# keyboard.net
KiCad netlist of a schematic drawn in EAGLE
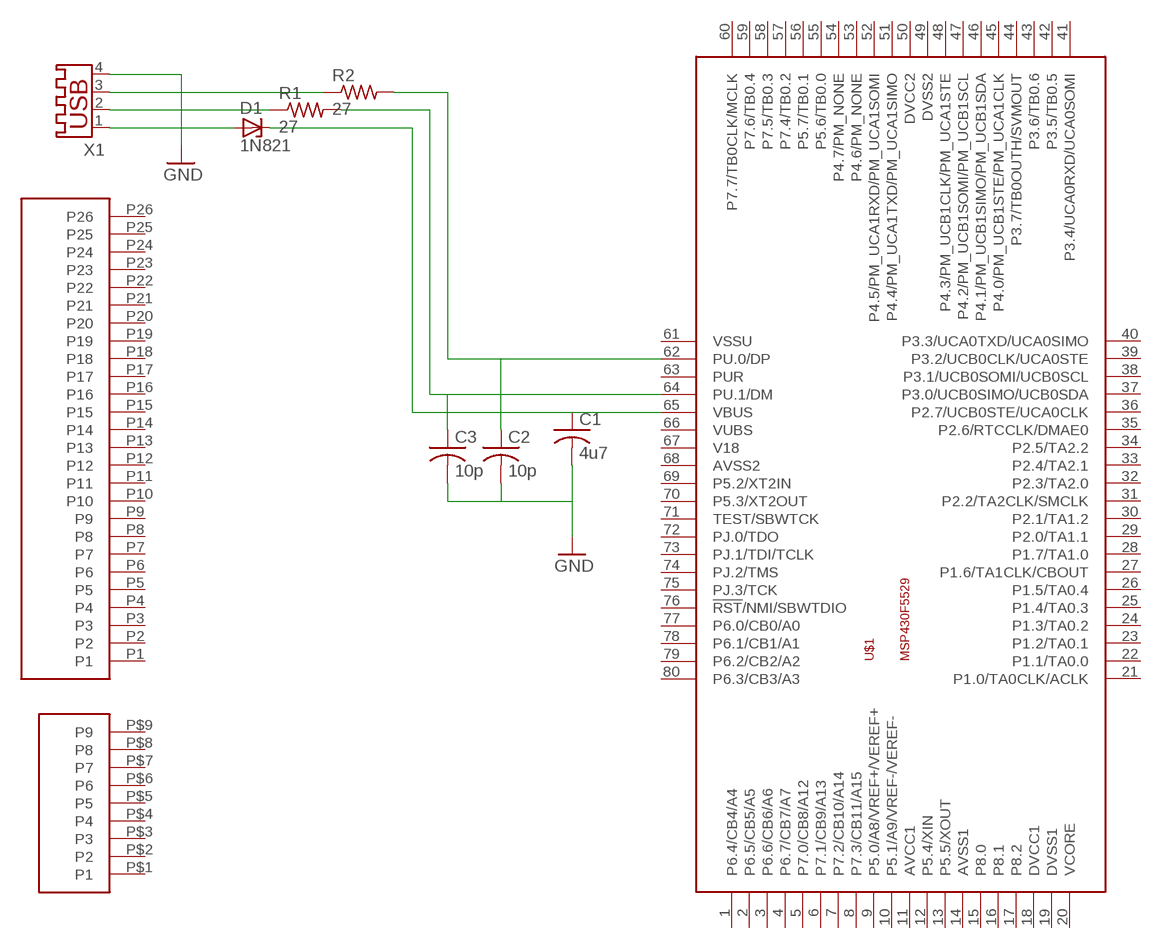
[diagram p0: schematic, sheet 1]

(export (version "E")
  (design (tool "Eeschema 10.0.6"))
  (components
    (comp (ref "C1")
      (value "4u7")
      (footprint "eagle-import:C0805")
      (libsource (lib "eagle-import") (part "C-USC0805"))
    )
    (comp (ref "C2")
      (value "10p")
      (footprint "eagle-import:C0805")
      (libsource (lib "eagle-import") (part "C-USC0805"))
    )
    (comp (ref "C3")
      (value "10p")
      (footprint "eagle-import:C0805")
      (libsource (lib "eagle-import") (part "C-USC0805"))
    )
    (comp (ref "D1")
      (value "1N821")
      (footprint "eagle-import:DO35Z10")
      (libsource (lib "eagle-import") (part "1N821"))
    )
    (comp (ref "R1")
      (value "27")
      (footprint "eagle-import:R0603")
      (libsource (lib "eagle-import") (part "R-US_R0603"))
    )
    (comp (ref "R2")
      (value "27")
      (footprint "eagle-import:R0603")
      (libsource (lib "eagle-import") (part "R-US_R0603"))
    )
    (comp (ref "U$1")
      (value "MSP430F5529")
      (footprint "eagle-import:PN_S-PQFP-G80")
      (libsource (lib "eagle-import") (part "MSP430F5529"))
    )
    (comp (ref "U$2")
      (value "52808-267126")
      (footprint "eagle-import:SD-52808-025")
      (libsource (lib "eagle-import") (part "52808-267126"))
    )
    (comp (ref "U$3")
      (value "52806-0910")
      (footprint "eagle-import:SD-52806-09")
      (libsource (lib "eagle-import") (part "52806-0910"))
    )
    (comp (ref "X1")
      (value "USB-A003")
      (footprint "eagle-import:USB-A003")
      (libsource (lib "eagle-import") (part "USB-A003"))
    )
  )
  (nets
    (net (code "1") (name "GND") (class "Default")
      (node (ref "C1") (pin "2") (pinfunction "2_2") (pintype "passive"))
      (node (ref "C2") (pin "2") (pinfunction "2_2") (pintype "passive"))
      (node (ref "C3") (pin "2") (pinfunction "2_2") (pintype "passive"))
      (node (ref "X1") (pin "4") (pinfunction "4_4") (pintype "passive"))
    )
    (net (code "2") (name "Net-(D1-PadA)") (class "Default")
      (node (ref "D1") (pin "A") (pinfunction "A_A") (pintype "passive"))
      (node (ref "X1") (pin "1") (pinfunction "1_1") (pintype "passive"))
    )
    (net (code "3") (name "Net-(R1-Pad1)") (class "Default")
      (node (ref "R1") (pin "1") (pinfunction "1_1") (pintype "passive"))
      (node (ref "X1") (pin "2") (pinfunction "2_2") (pintype "passive"))
    )
    (net (code "4") (name "Net-(R2-Pad1)") (class "Default")
      (node (ref "R2") (pin "1") (pinfunction "1_1") (pintype "passive"))
      (node (ref "X1") (pin "3") (pinfunction "3_3") (pintype "passive"))
    )
    (net (code "5") (name "Net-(U$1-PU.0{slash}DP)") (class "Default")
      (node (ref "C2") (pin "1") (pinfunction "1_1") (pintype "passive"))
      (node (ref "R2") (pin "2") (pinfunction "2_2") (pintype "passive"))
      (node (ref "U$1") (pin "62") (pinfunction "PU.0/DP_62") (pintype "bidirectional"))
    )
    (net (code "6") (name "Net-(U$1-PU.1{slash}DM)") (class "Default")
      (node (ref "C3") (pin "1") (pinfunction "1_1") (pintype "passive"))
      (node (ref "R1") (pin "2") (pinfunction "2_2") (pintype "passive"))
      (node (ref "U$1") (pin "64") (pinfunction "PU.1/DM_64") (pintype "bidirectional"))
    )
    (net (code "7") (name "Net-(U$1-VBUS)") (class "Default")
      (node (ref "C1") (pin "1") (pinfunction "1_1") (pintype "passive"))
      (node (ref "D1") (pin "C") (pinfunction "C_C") (pintype "passive"))
      (node (ref "U$1") (pin "65") (pinfunction "VBUS_65") (pintype "bidirectional"))
    )
    (net (code "8") (name "unconnected-(U$1-AVCC1-Pad11)") (class "Default")
      (node (ref "U$1") (pin "11") (pinfunction "AVCC1_11") (pintype "bidirectional"))
    )
    (net (code "9") (name "unconnected-(U$1-AVSS1-Pad14)") (class "Default")
      (node (ref "U$1") (pin "14") (pinfunction "AVSS1_14") (pintype "bidirectional"))
    )
    (net (code "10") (name "unconnected-(U$1-AVSS2-Pad68)") (class "Default")
      (node (ref "U$1") (pin "68") (pinfunction "AVSS2_68") (pintype "bidirectional"))
    )
    (net (code "11") (name "unconnected-(U$1-DVCC1-Pad18)") (class "Default")
      (node (ref "U$1") (pin "18") (pinfunction "DVCC1_18") (pintype "bidirectional"))
    )
    (net (code "12") (name "unconnected-(U$1-DVCC2-Pad50)") (class "Default")
      (node (ref "U$1") (pin "50") (pinfunction "DVCC2_50") (pintype "bidirectional"))
    )
    (net (code "13") (name "unconnected-(U$1-DVSS1-Pad19)") (class "Default")
      (node (ref "U$1") (pin "19") (pinfunction "DVSS1_19") (pintype "bidirectional"))
    )
    (net (code "14") (name "unconnected-(U$1-DVSS2-Pad49)") (class "Default")
      (node (ref "U$1") (pin "49") (pinfunction "DVSS2_49") (pintype "bidirectional"))
    )
    (net (code "15") (name "unconnected-(U$1-P1.0{slash}TA0CLK{slash}ACLK-Pad21)") (class "Default")
      (node (ref "U$1") (pin "21") (pinfunction "P1.0/TA0CLK/ACLK_21") (pintype "bidirectional"))
    )
    (net (code "16") (name "unconnected-(U$1-P1.1{slash}TA0.0-Pad22)") (class "Default")
      (node (ref "U$1") (pin "22") (pinfunction "P1.1/TA0.0_22") (pintype "bidirectional"))
    )
    (net (code "17") (name "unconnected-(U$1-P1.2{slash}TA0.1-Pad23)") (class "Default")
      (node (ref "U$1") (pin "23") (pinfunction "P1.2/TA0.1_23") (pintype "bidirectional"))
    )
    (net (code "18") (name "unconnected-(U$1-P1.3{slash}TA0.2-Pad24)") (class "Default")
      (node (ref "U$1") (pin "24") (pinfunction "P1.3/TA0.2_24") (pintype "bidirectional"))
    )
    (net (code "19") (name "unconnected-(U$1-P1.4{slash}TA0.3-Pad25)") (class "Default")
      (node (ref "U$1") (pin "25") (pinfunction "P1.4/TA0.3_25") (pintype "bidirectional"))
    )
    (net (code "20") (name "unconnected-(U$1-P1.5{slash}TA0.4-Pad26)") (class "Default")
      (node (ref "U$1") (pin "26") (pinfunction "P1.5/TA0.4_26") (pintype "bidirectional"))
    )
    (net (code "21") (name "unconnected-(U$1-P1.6{slash}TA1CLK{slash}CBOUT-Pad27)") (class "Default")
      (node (ref "U$1") (pin "27") (pinfunction "P1.6/TA1CLK/CBOUT_27") (pintype "bidirectional"))
    )
    (net (code "22") (name "unconnected-(U$1-P1.7{slash}TA1.0-Pad28)") (class "Default")
      (node (ref "U$1") (pin "28") (pinfunction "P1.7/TA1.0_28") (pintype "bidirectional"))
    )
    (net (code "23") (name "unconnected-(U$1-P2.0{slash}TA1.1-Pad29)") (class "Default")
      (node (ref "U$1") (pin "29") (pinfunction "P2.0/TA1.1_29") (pintype "bidirectional"))
    )
    (net (code "24") (name "unconnected-(U$1-P2.1{slash}TA1.2-Pad30)") (class "Default")
      (node (ref "U$1") (pin "30") (pinfunction "P2.1/TA1.2_30") (pintype "bidirectional"))
    )
    (net (code "25") (name "unconnected-(U$1-P2.2{slash}TA2CLK{slash}SMCLK-Pad31)") (class "Default")
      (node (ref "U$1") (pin "31") (pinfunction "P2.2/TA2CLK/SMCLK_31") (pintype "bidirectional"))
    )
    (net (code "26") (name "unconnected-(U$1-P2.3{slash}TA2.0-Pad32)") (class "Default")
      (node (ref "U$1") (pin "32") (pinfunction "P2.3/TA2.0_32") (pintype "bidirectional"))
    )
    (net (code "27") (name "unconnected-(U$1-P2.4{slash}TA2.1-Pad33)") (class "Default")
      (node (ref "U$1") (pin "33") (pinfunction "P2.4/TA2.1_33") (pintype "bidirectional"))
    )
    (net (code "28") (name "unconnected-(U$1-P2.5{slash}TA2.2-Pad34)") (class "Default")
      (node (ref "U$1") (pin "34") (pinfunction "P2.5/TA2.2_34") (pintype "bidirectional"))
    )
    (net (code "29") (name "unconnected-(U$1-P2.6{slash}RTCCLK{slash}DMAE0-Pad35)") (class "Default")
      (node (ref "U$1") (pin "35") (pinfunction "P2.6/RTCCLK/DMAE0_35") (pintype "bidirectional"))
    )
    (net (code "30") (name "unconnected-(U$1-P2.7{slash}UCB0STE{slash}UCA0CLK-Pad36)") (class "Default")
      (node (ref "U$1") (pin "36") (pinfunction "P2.7/UCB0STE/UCA0CLK_36") (pintype "bidirectional"))
    )
    (net (code "31") (name "unconnected-(U$1-P3.0{slash}UCB0SIMO{slash}UCB0SDA-Pad37)") (class "Default")
      (node (ref "U$1") (pin "37") (pinfunction "P3.0/UCB0SIMO/UCB0SDA_37") (pintype "bidirectional"))
    )
    (net (code "32") (name "unconnected-(U$1-P3.1{slash}UCB0SOMI{slash}UCB0SCL-Pad38)") (class "Default")
      (node (ref "U$1") (pin "38") (pinfunction "P3.1/UCB0SOMI/UCB0SCL_38") (pintype "bidirectional"))
    )
    (net (code "33") (name "unconnected-(U$1-P3.2{slash}UCB0CLK{slash}UCA0STE-Pad39)") (class "Default")
      (node (ref "U$1") (pin "39") (pinfunction "P3.2/UCB0CLK/UCA0STE_39") (pintype "bidirectional"))
    )
    (net (code "34") (name "unconnected-(U$1-P3.3{slash}UCA0TXD{slash}UCA0SIMO-Pad40)") (class "Default")
      (node (ref "U$1") (pin "40") (pinfunction "P3.3/UCA0TXD/UCA0SIMO_40") (pintype "bidirectional"))
    )
    (net (code "35") (name "unconnected-(U$1-P3.4{slash}UCA0RXD{slash}UCA0SOMI-Pad41)") (class "Default")
      (node (ref "U$1") (pin "41") (pinfunction "P3.4/UCA0RXD/UCA0SOMI_41") (pintype "bidirectional"))
    )
    (net (code "36") (name "unconnected-(U$1-P3.5{slash}TB0.5-Pad42)") (class "Default")
      (node (ref "U$1") (pin "42") (pinfunction "P3.5/TB0.5_42") (pintype "bidirectional"))
    )
    (net (code "37") (name "unconnected-(U$1-P3.6{slash}TB0.6-Pad43)") (class "Default")
      (node (ref "U$1") (pin "43") (pinfunction "P3.6/TB0.6_43") (pintype "bidirectional"))
    )
    (net (code "38") (name "unconnected-(U$1-P3.7{slash}TB0OUTH{slash}SVMOUT-Pad44)") (class "Default")
      (node (ref "U$1") (pin "44") (pinfunction "P3.7/TB0OUTH/SVMOUT_44") (pintype "bidirectional"))
    )
    (net (code "39") (name "unconnected-(U$1-P4.0{slash}PM_UCB1STE{slash}PM_UCA1CLK-Pad45)") (class "Default")
      (node (ref "U$1") (pin "45") (pinfunction "P4.0/PM_UCB1STE/PM_UCA1CLK_45") (pintype "bidirectional"))
    )
    (net (code "40") (name "unconnected-(U$1-P4.1{slash}PM_UCB1SIMO{slash}PM_UCB1SDA-Pad46)") (class "Default")
      (node (ref "U$1") (pin "46") (pinfunction "P4.1/PM_UCB1SIMO/PM_UCB1SDA_46") (pintype "bidirectional"))
    )
    (net (code "41") (name "unconnected-(U$1-P4.2{slash}PM_UCB1SOMI{slash}PM_UCB1SCL-Pad47)") (class "Default")
      (node (ref "U$1") (pin "47") (pinfunction "P4.2/PM_UCB1SOMI/PM_UCB1SCL_47") (pintype "bidirectional"))
    )
    (net (code "42") (name "unconnected-(U$1-P4.3{slash}PM_UCB1CLK{slash}PM_UCA1STE-Pad48)") (class "Default")
      (node (ref "U$1") (pin "48") (pinfunction "P4.3/PM_UCB1CLK/PM_UCA1STE_48") (pintype "bidirectional"))
    )
    (net (code "43") (name "unconnected-(U$1-P4.4{slash}PM_UCA1TXD{slash}PM_UCA1SIMO-Pad51)") (class "Default")
      (node (ref "U$1") (pin "51") (pinfunction "P4.4/PM_UCA1TXD/PM_UCA1SIMO_51") (pintype "bidirectional"))
    )
    (net (code "44") (name "unconnected-(U$1-P4.5{slash}PM_UCA1RXD{slash}PM_UCA1SOMI-Pad52)") (class "Default")
      (node (ref "U$1") (pin "52") (pinfunction "P4.5/PM_UCA1RXD/PM_UCA1SOMI_52") (pintype "bidirectional"))
    )
    (net (code "45") (name "unconnected-(U$1-P4.6{slash}PM_NONE-Pad53)") (class "Default")
      (node (ref "U$1") (pin "53") (pinfunction "P4.6/PM_NONE_53") (pintype "bidirectional"))
    )
    (net (code "46") (name "unconnected-(U$1-P4.7{slash}PM_NONE-Pad54)") (class "Default")
      (node (ref "U$1") (pin "54") (pinfunction "P4.7/PM_NONE_54") (pintype "bidirectional"))
    )
    (net (code "47") (name "unconnected-(U$1-P5.0{slash}A8{slash}VREF+{slash}VEREF+-Pad9)") (class "Default")
      (node (ref "U$1") (pin "9") (pinfunction "P5.0/A8/VREF+/VEREF+_9") (pintype "bidirectional"))
    )
    (net (code "48") (name "unconnected-(U$1-P5.1{slash}A9{slash}VREF-{slash}VEREF--Pad10)") (class "Default")
      (node (ref "U$1") (pin "10") (pinfunction "P5.1/A9/VREF-/VEREF-_10") (pintype "bidirectional"))
    )
    (net (code "49") (name "unconnected-(U$1-P5.2{slash}XT2IN-Pad69)") (class "Default")
      (node (ref "U$1") (pin "69") (pinfunction "P5.2/XT2IN_69") (pintype "bidirectional"))
    )
    (net (code "50") (name "unconnected-(U$1-P5.3{slash}XT2OUT-Pad70)") (class "Default")
      (node (ref "U$1") (pin "70") (pinfunction "P5.3/XT2OUT_70") (pintype "bidirectional"))
    )
    (net (code "51") (name "unconnected-(U$1-P5.4{slash}XIN-Pad12)") (class "Default")
      (node (ref "U$1") (pin "12") (pinfunction "P5.4/XIN_12") (pintype "bidirectional"))
    )
    (net (code "52") (name "unconnected-(U$1-P5.5{slash}XOUT-Pad13)") (class "Default")
      (node (ref "U$1") (pin "13") (pinfunction "P5.5/XOUT_13") (pintype "bidirectional"))
    )
    (net (code "53") (name "unconnected-(U$1-P5.6{slash}TB0.0-Pad55)") (class "Default")
      (node (ref "U$1") (pin "55") (pinfunction "P5.6/TB0.0_55") (pintype "bidirectional"))
    )
    (net (code "54") (name "unconnected-(U$1-P5.7{slash}TB0.1-Pad56)") (class "Default")
      (node (ref "U$1") (pin "56") (pinfunction "P5.7/TB0.1_56") (pintype "bidirectional"))
    )
    (net (code "55") (name "unconnected-(U$1-P6.0{slash}CB0{slash}A0-Pad77)") (class "Default")
      (node (ref "U$1") (pin "77") (pinfunction "P6.0/CB0/A0_77") (pintype "bidirectional"))
    )
    (net (code "56") (name "unconnected-(U$1-P6.1{slash}CB1{slash}A1-Pad78)") (class "Default")
      (node (ref "U$1") (pin "78") (pinfunction "P6.1/CB1/A1_78") (pintype "bidirectional"))
    )
    (net (code "57") (name "unconnected-(U$1-P6.2{slash}CB2{slash}A2-Pad79)") (class "Default")
      (node (ref "U$1") (pin "79") (pinfunction "P6.2/CB2/A2_79") (pintype "bidirectional"))
    )
    (net (code "58") (name "unconnected-(U$1-P6.3{slash}CB3{slash}A3-Pad80)") (class "Default")
      (node (ref "U$1") (pin "80") (pinfunction "P6.3/CB3/A3_80") (pintype "bidirectional"))
    )
    (net (code "59") (name "unconnected-(U$1-P6.4{slash}CB4{slash}A4-Pad1)") (class "Default")
      (node (ref "U$1") (pin "1") (pinfunction "P6.4/CB4/A4_1") (pintype "bidirectional"))
    )
    (net (code "60") (name "unconnected-(U$1-P6.5{slash}CB5{slash}A5-Pad2)") (class "Default")
      (node (ref "U$1") (pin "2") (pinfunction "P6.5/CB5/A5_2") (pintype "bidirectional"))
    )
    (net (code "61") (name "unconnected-(U$1-P6.6{slash}CB6{slash}A6-Pad3)") (class "Default")
      (node (ref "U$1") (pin "3") (pinfunction "P6.6/CB6/A6_3") (pintype "bidirectional"))
    )
    (net (code "62") (name "unconnected-(U$1-P6.7{slash}CB7{slash}A7-Pad4)") (class "Default")
      (node (ref "U$1") (pin "4") (pinfunction "P6.7/CB7/A7_4") (pintype "bidirectional"))
    )
    (net (code "63") (name "unconnected-(U$1-P7.0{slash}CB8{slash}A12-Pad5)") (class "Default")
      (node (ref "U$1") (pin "5") (pinfunction "P7.0/CB8/A12_5") (pintype "bidirectional"))
    )
    (net (code "64") (name "unconnected-(U$1-P7.1{slash}CB9{slash}A13-Pad6)") (class "Default")
      (node (ref "U$1") (pin "6") (pinfunction "P7.1/CB9/A13_6") (pintype "bidirectional"))
    )
    (net (code "65") (name "unconnected-(U$1-P7.2{slash}CB10{slash}A14-Pad7)") (class "Default")
      (node (ref "U$1") (pin "7") (pinfunction "P7.2/CB10/A14_7") (pintype "bidirectional"))
    )
    (net (code "66") (name "unconnected-(U$1-P7.3{slash}CB11{slash}A15-Pad8)") (class "Default")
      (node (ref "U$1") (pin "8") (pinfunction "P7.3/CB11/A15_8") (pintype "bidirectional"))
    )
    (net (code "67") (name "unconnected-(U$1-P7.4{slash}TB0.2-Pad57)") (class "Default")
      (node (ref "U$1") (pin "57") (pinfunction "P7.4/TB0.2_57") (pintype "bidirectional"))
    )
    (net (code "68") (name "unconnected-(U$1-P7.5{slash}TB0.3-Pad58)") (class "Default")
      (node (ref "U$1") (pin "58") (pinfunction "P7.5/TB0.3_58") (pintype "bidirectional"))
    )
    (net (code "69") (name "unconnected-(U$1-P7.6{slash}TB0.4-Pad59)") (class "Default")
      (node (ref "U$1") (pin "59") (pinfunction "P7.6/TB0.4_59") (pintype "bidirectional"))
    )
    (net (code "70") (name "unconnected-(U$1-P7.7{slash}TB0CLK{slash}MCLK-Pad60)") (class "Default")
      (node (ref "U$1") (pin "60") (pinfunction "P7.7/TB0CLK/MCLK_60") (pintype "bidirectional"))
    )
    (net (code "71") (name "unconnected-(U$1-P8.0-Pad15)") (class "Default")
      (node (ref "U$1") (pin "15") (pinfunction "P8.0_15") (pintype "bidirectional"))
    )
    (net (code "72") (name "unconnected-(U$1-P8.1-Pad16)") (class "Default")
      (node (ref "U$1") (pin "16") (pinfunction "P8.1_16") (pintype "bidirectional"))
    )
    (net (code "73") (name "unconnected-(U$1-P8.2-Pad17)") (class "Default")
      (node (ref "U$1") (pin "17") (pinfunction "P8.2_17") (pintype "bidirectional"))
    )
    (net (code "74") (name "unconnected-(U$1-PJ.0{slash}TDO-Pad72)") (class "Default")
      (node (ref "U$1") (pin "72") (pinfunction "PJ.0/TDO_72") (pintype "bidirectional"))
    )
    (net (code "75") (name "unconnected-(U$1-PJ.1{slash}TDI{slash}TCLK-Pad73)") (class "Default")
      (node (ref "U$1") (pin "73") (pinfunction "PJ.1/TDI/TCLK_73") (pintype "bidirectional"))
    )
    (net (code "76") (name "unconnected-(U$1-PJ.2{slash}TMS-Pad74)") (class "Default")
      (node (ref "U$1") (pin "74") (pinfunction "PJ.2/TMS_74") (pintype "bidirectional"))
    )
    (net (code "77") (name "unconnected-(U$1-PJ.3{slash}TCK-Pad75)") (class "Default")
      (node (ref "U$1") (pin "75") (pinfunction "PJ.3/TCK_75") (pintype "bidirectional"))
    )
    (net (code "78") (name "unconnected-(U$1-PUR-Pad63)") (class "Default")
      (node (ref "U$1") (pin "63") (pinfunction "PUR_63") (pintype "bidirectional"))
    )
    (net (code "79") (name "unconnected-(U$1-TEST{slash}SBWTCK-Pad71)") (class "Default")
      (node (ref "U$1") (pin "71") (pinfunction "TEST/SBWTCK_71") (pintype "bidirectional"))
    )
    (net (code "80") (name "unconnected-(U$1-V18-Pad67)") (class "Default")
      (node (ref "U$1") (pin "67") (pinfunction "V18_67") (pintype "bidirectional"))
    )
    (net (code "81") (name "unconnected-(U$1-VCORE-Pad20)") (class "Default")
      (node (ref "U$1") (pin "20") (pinfunction "VCORE_20") (pintype "bidirectional"))
    )
    (net (code "82") (name "unconnected-(U$1-VSSU-Pad61)") (class "Default")
      (node (ref "U$1") (pin "61") (pinfunction "VSSU_61") (pintype "bidirectional"))
    )
    (net (code "83") (name "unconnected-(U$1-VUBS-Pad66)") (class "Default")
      (node (ref "U$1") (pin "66") (pinfunction "VUBS_66") (pintype "bidirectional"))
    )
    (net (code "84") (name "unconnected-(U$1-~{RST}{slash}NMI{slash}SBWTDIO-Pad76)") (class "Default")
      (node (ref "U$1") (pin "76") (pinfunction "~{RST}/NMI/SBWTDIO_76") (pintype "bidirectional"))
    )
    (net (code "85") (name "unconnected-(U$2-PadP1)") (class "Default")
      (node (ref "U$2") (pin "P1") (pinfunction "P1_P1") (pintype "bidirectional"))
    )
    (net (code "86") (name "unconnected-(U$2-PadP2)") (class "Default")
      (node (ref "U$2") (pin "P2") (pinfunction "P2_P2") (pintype "bidirectional"))
    )
    (net (code "87") (name "unconnected-(U$2-PadP3)") (class "Default")
      (node (ref "U$2") (pin "P3") (pinfunction "P3_P3") (pintype "bidirectional"))
    )
    (net (code "88") (name "unconnected-(U$2-PadP4)") (class "Default")
      (node (ref "U$2") (pin "P4") (pinfunction "P4_P4") (pintype "bidirectional"))
    )
    (net (code "89") (name "unconnected-(U$2-PadP5)") (class "Default")
      (node (ref "U$2") (pin "P5") (pinfunction "P5_P5") (pintype "bidirectional"))
    )
    (net (code "90") (name "unconnected-(U$2-PadP6)") (class "Default")
      (node (ref "U$2") (pin "P6") (pinfunction "P6_P6") (pintype "bidirectional"))
    )
    (net (code "91") (name "unconnected-(U$2-PadP7)") (class "Default")
      (node (ref "U$2") (pin "P7") (pinfunction "P7_P7") (pintype "bidirectional"))
    )
    (net (code "92") (name "unconnected-(U$2-PadP8)") (class "Default")
      (node (ref "U$2") (pin "P8") (pinfunction "P8_P8") (pintype "bidirectional"))
    )
    (net (code "93") (name "unconnected-(U$2-PadP9)") (class "Default")
      (node (ref "U$2") (pin "P9") (pinfunction "P9_P9") (pintype "bidirectional"))
    )
    (net (code "94") (name "unconnected-(U$2-PadP10)") (class "Default")
      (node (ref "U$2") (pin "P10") (pinfunction "P10_P10") (pintype "bidirectional"))
    )
    (net (code "95") (name "unconnected-(U$2-PadP11)") (class "Default")
      (node (ref "U$2") (pin "P11") (pinfunction "P11_P11") (pintype "bidirectional"))
    )
    (net (code "96") (name "unconnected-(U$2-PadP12)") (class "Default")
      (node (ref "U$2") (pin "P12") (pinfunction "P12_P12") (pintype "bidirectional"))
    )
    (net (code "97") (name "unconnected-(U$2-PadP13)") (class "Default")
      (node (ref "U$2") (pin "P13") (pinfunction "P13_P13") (pintype "bidirectional"))
    )
    (net (code "98") (name "unconnected-(U$2-PadP14)") (class "Default")
      (node (ref "U$2") (pin "P14") (pinfunction "P14_P14") (pintype "bidirectional"))
    )
    (net (code "99") (name "unconnected-(U$2-PadP15)") (class "Default")
      (node (ref "U$2") (pin "P15") (pinfunction "P15_P15") (pintype "bidirectional"))
    )
    (net (code "100") (name "unconnected-(U$2-PadP16)") (class "Default")
      (node (ref "U$2") (pin "P16") (pinfunction "P16_P16") (pintype "bidirectional"))
    )
    (net (code "101") (name "unconnected-(U$2-PadP17)") (class "Default")
      (node (ref "U$2") (pin "P17") (pinfunction "P17_P17") (pintype "bidirectional"))
    )
    (net (code "102") (name "unconnected-(U$2-PadP18)") (class "Default")
      (node (ref "U$2") (pin "P18") (pinfunction "P18_P18") (pintype "bidirectional"))
    )
    (net (code "103") (name "unconnected-(U$2-PadP19)") (class "Default")
      (node (ref "U$2") (pin "P19") (pinfunction "P19_P19") (pintype "bidirectional"))
    )
    (net (code "104") (name "unconnected-(U$2-PadP20)") (class "Default")
      (node (ref "U$2") (pin "P20") (pinfunction "P20_P20") (pintype "bidirectional"))
    )
    (net (code "105") (name "unconnected-(U$2-PadP21)") (class "Default")
      (node (ref "U$2") (pin "P21") (pinfunction "P21_P21") (pintype "bidirectional"))
    )
    (net (code "106") (name "unconnected-(U$2-PadP22)") (class "Default")
      (node (ref "U$2") (pin "P22") (pinfunction "P22_P22") (pintype "bidirectional"))
    )
    (net (code "107") (name "unconnected-(U$2-PadP23)") (class "Default")
      (node (ref "U$2") (pin "P23") (pinfunction "P23_P23") (pintype "bidirectional"))
    )
    (net (code "108") (name "unconnected-(U$2-PadP24)") (class "Default")
      (node (ref "U$2") (pin "P24") (pinfunction "P24_P24") (pintype "bidirectional"))
    )
    (net (code "109") (name "unconnected-(U$2-PadP25)") (class "Default")
      (node (ref "U$2") (pin "P25") (pinfunction "P25_P25") (pintype "bidirectional"))
    )
    (net (code "110") (name "unconnected-(U$2-PadP26)") (class "Default")
      (node (ref "U$2") (pin "P26") (pinfunction "P26_P26") (pintype "bidirectional"))
    )
    (net (code "111") (name "unconnected-(U$3-P1-PadP$1)") (class "Default")
      (node (ref "U$3") (pin "P$1") (pinfunction "P1_P$1") (pintype "bidirectional"))
    )
    (net (code "112") (name "unconnected-(U$3-P2-PadP$2)") (class "Default")
      (node (ref "U$3") (pin "P$2") (pinfunction "P2_P$2") (pintype "bidirectional"))
    )
    (net (code "113") (name "unconnected-(U$3-P3-PadP$3)") (class "Default")
      (node (ref "U$3") (pin "P$3") (pinfunction "P3_P$3") (pintype "bidirectional"))
    )
    (net (code "114") (name "unconnected-(U$3-P4-PadP$4)") (class "Default")
      (node (ref "U$3") (pin "P$4") (pinfunction "P4_P$4") (pintype "bidirectional"))
    )
    (net (code "115") (name "unconnected-(U$3-P5-PadP$5)") (class "Default")
      (node (ref "U$3") (pin "P$5") (pinfunction "P5_P$5") (pintype "bidirectional"))
    )
    (net (code "116") (name "unconnected-(U$3-P6-PadP$6)") (class "Default")
      (node (ref "U$3") (pin "P$6") (pinfunction "P6_P$6") (pintype "bidirectional"))
    )
    (net (code "117") (name "unconnected-(U$3-P7-PadP$7)") (class "Default")
      (node (ref "U$3") (pin "P$7") (pinfunction "P7_P$7") (pintype "bidirectional"))
    )
    (net (code "118") (name "unconnected-(U$3-P8-PadP$8)") (class "Default")
      (node (ref "U$3") (pin "P$8") (pinfunction "P8_P$8") (pintype "bidirectional"))
    )
    (net (code "119") (name "unconnected-(U$3-P9-PadP$9)") (class "Default")
      (node (ref "U$3") (pin "P$9") (pinfunction "P9_P$9") (pintype "bidirectional"))
    )
  )
)
